# Fly-Back.net
KiCad netlist of a schematic drawn in Altium Designer
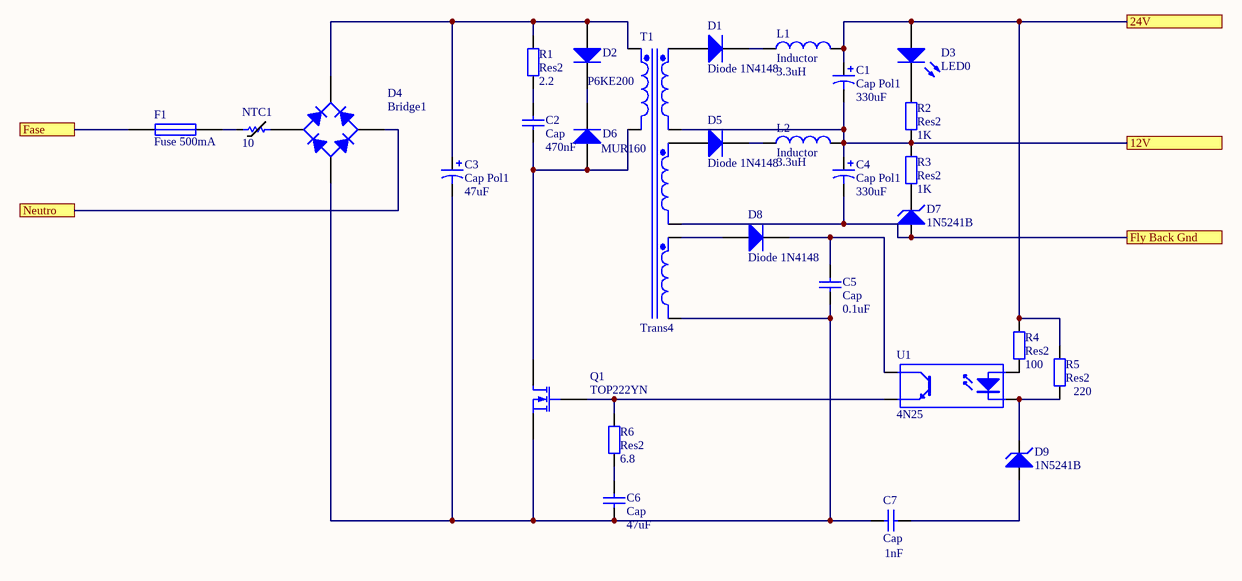
[diagram p0: Fly-Back.SchDoc]

(export (version "E")
  (design (tool "Eeschema 10.0.6"))
  (components
    (comp (ref "C1")
      (value "Cap Pol1")
      (footprint "RB7.6-15")
      (description "Polarized Capacitor (Radial)")
      (fields (field (name "ALTIUM_VALUE") "330uF") (field (name "PUBLISHER") "Altium Limited"))
      (libsource (lib "Miscellaneous Devices") (part "Cap Pol1"))
    )
    (comp (ref "C2")
      (value "Cap")
      (footprint "RAD-0.3")
      (description "Capacitor")
      (fields (field (name "ALTIUM_VALUE") "470nF") (field (name "PUBLISHER") "Altium Limited"))
      (libsource (lib "Miscellaneous Devices") (part "Cap"))
    )
    (comp (ref "C3")
      (value "Cap Pol1")
      (footprint "RB7.6-15")
      (description "Polarized Capacitor (Radial)")
      (fields (field (name "ALTIUM_VALUE") "47uF") (field (name "PUBLISHER") "Altium Limited"))
      (libsource (lib "Miscellaneous Devices") (part "Cap Pol1"))
    )
    (comp (ref "C4")
      (value "Cap Pol1")
      (footprint "RB7.6-15")
      (description "Polarized Capacitor (Radial)")
      (fields (field (name "ALTIUM_VALUE") "330uF") (field (name "PUBLISHER") "Altium Limited"))
      (libsource (lib "Miscellaneous Devices") (part "Cap Pol1"))
    )
    (comp (ref "C5")
      (value "Cap")
      (footprint "RAD-0.3")
      (description "Capacitor")
      (fields (field (name "ALTIUM_VALUE") "0.1uF") (field (name "PUBLISHER") "Altium Limited"))
      (libsource (lib "Miscellaneous Devices") (part "Cap"))
    )
    (comp (ref "C6")
      (value "Cap")
      (footprint "RAD-0.3")
      (description "Capacitor")
      (fields (field (name "ALTIUM_VALUE") "47uF") (field (name "PUBLISHER") "Altium Limited"))
      (libsource (lib "Miscellaneous Devices") (part "Cap"))
    )
    (comp (ref "C7")
      (value "Cap")
      (footprint "RAD-0.3")
      (description "Capacitor")
      (fields (field (name "ALTIUM_VALUE") "1nF") (field (name "PUBLISHER") "Altium Limited"))
      (libsource (lib "Miscellaneous Devices") (part "Cap"))
    )
    (comp (ref "D1")
      (value "Diode 1N4148")
      (footprint "DO-35")
      (description "High Conductance Fast Diode")
      (fields (field (name "PUBLISHER") "Altium Limited"))
      (libsource (lib "Miscellaneous Devices") (part "Diode 1N4148"))
    )
    (comp (ref "D2")
      (value "P6KE200")
      (footprint "DO-35")
      (description "High Conductance Fast Diode")
      (fields (field (name "PUBLISHER") "Altium Limited"))
      (libsource (lib "Miscellaneous Devices") (part "Diode 1N4148"))
    )
    (comp (ref "D3")
      (value "LED0")
      (footprint "LED-0")
      (description "Typical INFRARED GaAs LED")
      (fields (field (name "PUBLISHER") "Altium Limited"))
      (libsource (lib "Miscellaneous Devices") (part "LED0"))
    )
    (comp (ref "D4")
      (value "Bridge1")
      (footprint "D-38")
      (description "Full Wave Diode Bridge")
      (fields (field (name "PUBLISHER") "Altium Limited"))
      (libsource (lib "Miscellaneous Devices") (part "Bridge1"))
    )
    (comp (ref "D5")
      (value "Diode 1N4148")
      (footprint "DO-35")
      (description "High Conductance Fast Diode")
      (fields (field (name "PUBLISHER") "Altium Limited"))
      (libsource (lib "Miscellaneous Devices") (part "Diode 1N4148"))
    )
    (comp (ref "D6")
      (value "MUR160")
      (footprint "DO-35")
      (description "High Conductance Fast Diode")
      (fields (field (name "PUBLISHER") "Altium Limited"))
      (libsource (lib "Miscellaneous Devices") (part "Diode 1N4148"))
    )
    (comp (ref "D7")
      (value "Diodo Zener")
      (footprint "DO-41")
      (fields (field (name "VALOR") "1N5241B"))
      (libsource (lib "RUF-Dispositivos-Grales") (part "Diodo Zener"))
    )
    (comp (ref "D8")
      (value "Diode 1N4148")
      (footprint "DO-35")
      (description "High Conductance Fast Diode")
      (fields (field (name "PUBLISHER") "Altium Limited"))
      (libsource (lib "Miscellaneous Devices") (part "Diode 1N4148"))
    )
    (comp (ref "D9")
      (value "Diodo Zener")
      (footprint "DO-41")
      (fields (field (name "VALOR") "1N5241B"))
      (libsource (lib "RUF-Dispositivos-Grales") (part "Diodo Zener"))
    )
    (comp (ref "F1")
      (value "Fuse 500mA")
      (footprint "PIN-W2/E2.8")
      (description "Fuse")
      (fields (field (name "PUBLISHER") "Altium Limited"))
      (libsource (lib "Miscellaneous Devices") (part "Fuse 1"))
    )
    (comp (ref "L1")
      (value "Inductor")
      (footprint "0402-A")
      (fields (field (name "ALTIUM_VALUE") "3.3uH") (field (name "PUBLISHER") "Altium Limited"))
      (libsource (lib "Miscellaneous Devices") (part "Inductor"))
    )
    (comp (ref "L2")
      (value "Inductor")
      (footprint "0402-A")
      (fields (field (name "ALTIUM_VALUE") "3.3uH") (field (name "PUBLISHER") "Altium Limited"))
      (libsource (lib "Miscellaneous Devices") (part "Inductor"))
    )
    (comp (ref "NTC1")
      (value "Termistor NTC")
      (footprint "R0805")
      (description "Termistor NTC SMD")
      (fields (field (name "VALOR") "10"))
      (libsource (lib "RUF-Dispositivos-Grales") (part "Termistor NTC"))
    )
    (comp (ref "Q1")
      (value "TOP222YN")
      (footprint "E3")
      (description "N-Channel MOSFET")
      (fields (field (name "PUBLISHER") "Altium Limited"))
      (libsource (lib "Miscellaneous Devices") (part "MOSFET-N"))
    )
    (comp (ref "R1")
      (value "Res2")
      (footprint "AXIAL-0.4")
      (description "Resistor")
      (fields (field (name "ALTIUM_VALUE") "2.2") (field (name "PUBLISHER") "Altium Limited"))
      (libsource (lib "Miscellaneous Devices") (part "Res2"))
    )
    (comp (ref "R2")
      (value "Res2")
      (footprint "AXIAL-0.4")
      (description "Resistor")
      (fields (field (name "ALTIUM_VALUE") "1K") (field (name "PUBLISHER") "Altium Limited"))
      (libsource (lib "Miscellaneous Devices") (part "Res2"))
    )
    (comp (ref "R3")
      (value "Res2")
      (footprint "AXIAL-0.4")
      (description "Resistor")
      (fields (field (name "ALTIUM_VALUE") "1K") (field (name "PUBLISHER") "Altium Limited"))
      (libsource (lib "Miscellaneous Devices") (part "Res2"))
    )
    (comp (ref "R4")
      (value "Res2")
      (footprint "AXIAL-0.4")
      (description "Resistor")
      (fields (field (name "ALTIUM_VALUE") "100") (field (name "PUBLISHER") "Altium Limited"))
      (libsource (lib "Miscellaneous Devices") (part "Res2"))
    )
    (comp (ref "R5")
      (value "Res2")
      (footprint "AXIAL-0.4")
      (description "Resistor")
      (fields (field (name "ALTIUM_VALUE") "220") (field (name "PUBLISHER") "Altium Limited"))
      (libsource (lib "Miscellaneous Devices") (part "Res2"))
    )
    (comp (ref "R6")
      (value "Res2")
      (footprint "AXIAL-0.4")
      (description "Resistor")
      (fields (field (name "ALTIUM_VALUE") "6.8") (field (name "PUBLISHER") "Altium Limited"))
      (libsource (lib "Miscellaneous Devices") (part "Res2"))
    )
    (comp (ref "T1")
      (value "Trans4")
      (footprint "TRF_8")
      (description "Four-winding Transformer (Non-Ideal)")
      (fields (field (name "PUBLISHER") "Altium Limited"))
      (libsource (lib "Miscellaneous Devices") (part "Trans4"))
    )
    (comp (ref "U1")
      (value "4N25")
      (footprint "DIP-4")
      (description "4-Pin Phototransistor Optocoupler")
      (fields (field (name "PUBLISHER") "Altium Limited"))
      (libsource (lib "Miscellaneous Devices") (part "Optoisolator1"))
    )
  )
  (nets
    (net (code "1") (name "/12V") (class "Default")
      (node (ref "C1") (pin "2") (pinfunction "2_2") (pintype "passive"))
      (node (ref "C4") (pin "1") (pinfunction "1_1") (pintype "passive"))
      (node (ref "L2") (pin "2") (pinfunction "2_2") (pintype "passive"))
      (node (ref "R2") (pin "1") (pinfunction "1_1") (pintype "passive"))
      (node (ref "R3") (pin "2") (pinfunction "2_2") (pintype "passive"))
      (node (ref "T1") (pin "4") (pinfunction "Sec1-_4") (pintype "passive"))
    )
    (net (code "2") (name "/24V") (class "Default")
      (node (ref "C1") (pin "1") (pinfunction "1_1") (pintype "passive"))
      (node (ref "D3") (pin "1") (pinfunction "A_1") (pintype "passive"))
      (node (ref "L1") (pin "2") (pinfunction "2_2") (pintype "passive"))
      (node (ref "R4") (pin "2") (pinfunction "2_2") (pintype "passive"))
      (node (ref "R5") (pin "2") (pinfunction "2_2") (pintype "passive"))
    )
    (net (code "3") (name "/Fase") (class "Default")
      (node (ref "F1") (pin "1") (pinfunction "1_1") (pintype "passive"))
    )
    (net (code "4") (name "/Fly Back Gnd") (class "Default")
      (node (ref "C4") (pin "2") (pinfunction "2_2") (pintype "passive"))
      (node (ref "D7") (pin "1") (pinfunction "A_1") (pintype "passive"))
      (node (ref "T1") (pin "6") (pinfunction "Sec2-_6") (pintype "passive"))
    )
    (net (code "5") (name "/Neutro") (class "Default")
      (node (ref "D4") (pin "2") (pinfunction "C_2") (pintype "passive"))
    )
    (net (code "6") (name "Net-(C2-Pad2)") (class "Default")
      (node (ref "C2") (pin "2") (pinfunction "2_2") (pintype "passive"))
      (node (ref "R1") (pin "1") (pinfunction "1_1") (pintype "passive"))
    )
    (net (code "7") (name "Net-(C6-Pad2)") (class "Default")
      (node (ref "C6") (pin "2") (pinfunction "2_2") (pintype "passive"))
      (node (ref "R6") (pin "1") (pinfunction "1_1") (pintype "passive"))
    )
    (net (code "8") (name "Net-(D1-A)") (class "Default")
      (node (ref "D1") (pin "1") (pinfunction "A_1") (pintype "passive"))
      (node (ref "T1") (pin "3") (pinfunction "Sec1+_3") (pintype "passive"))
    )
    (net (code "9") (name "Net-(D1-K)") (class "Default")
      (node (ref "D1") (pin "2") (pinfunction "K_2") (pintype "passive"))
      (node (ref "L1") (pin "1") (pinfunction "1_1") (pintype "passive"))
    )
    (net (code "10") (name "Net-(D2-A)") (class "Default")
      (node (ref "C3") (pin "1") (pinfunction "1_1") (pintype "passive"))
      (node (ref "D2") (pin "1") (pinfunction "A_1") (pintype "passive"))
      (node (ref "D4") (pin "1") (pinfunction "K_1") (pintype "passive"))
      (node (ref "R1") (pin "2") (pinfunction "2_2") (pintype "passive"))
      (node (ref "T1") (pin "1") (pinfunction "Pri+_1") (pintype "passive"))
    )
    (net (code "11") (name "Net-(D2-K)") (class "Default")
      (node (ref "D2") (pin "2") (pinfunction "K_2") (pintype "passive"))
      (node (ref "D6") (pin "2") (pinfunction "K_2") (pintype "passive"))
    )
    (net (code "12") (name "Net-(D3-K)") (class "Default")
      (node (ref "D3") (pin "2") (pinfunction "K_2") (pintype "passive"))
      (node (ref "R2") (pin "2") (pinfunction "2_2") (pintype "passive"))
    )
    (net (code "13") (name "Net-(D4-A)") (class "Default")
      (node (ref "C3") (pin "2") (pinfunction "2_2") (pintype "passive"))
      (node (ref "C5") (pin "1") (pinfunction "1_1") (pintype "passive"))
      (node (ref "C6") (pin "1") (pinfunction "1_1") (pintype "passive"))
      (node (ref "C7") (pin "1") (pinfunction "1_1") (pintype "passive"))
      (node (ref "D4") (pin "3") (pinfunction "A_3") (pintype "passive"))
      (node (ref "Q1") (pin "3") (pinfunction "S_3") (pintype "passive"))
      (node (ref "T1") (pin "8") (pinfunction "Sec3-_8") (pintype "passive"))
    )
    (net (code "14") (name "Net-(D4-C-Pad4)") (class "Default")
      (node (ref "D4") (pin "4") (pinfunction "C_4") (pintype "passive"))
      (node (ref "NTC1") (pin "1") (pinfunction "1_1") (pintype "passive"))
    )
    (net (code "15") (name "Net-(D5-A)") (class "Default")
      (node (ref "D5") (pin "1") (pinfunction "A_1") (pintype "passive"))
      (node (ref "T1") (pin "5") (pinfunction "Sec2+_5") (pintype "passive"))
    )
    (net (code "16") (name "Net-(D5-K)") (class "Default")
      (node (ref "D5") (pin "2") (pinfunction "K_2") (pintype "passive"))
      (node (ref "L2") (pin "1") (pinfunction "1_1") (pintype "passive"))
    )
    (net (code "17") (name "Net-(D6-A)") (class "Default")
      (node (ref "C2") (pin "1") (pinfunction "1_1") (pintype "passive"))
      (node (ref "D6") (pin "1") (pinfunction "A_1") (pintype "passive"))
      (node (ref "Q1") (pin "1") (pinfunction "D_1") (pintype "passive"))
      (node (ref "T1") (pin "2") (pinfunction "Pri-_2") (pintype "passive"))
    )
    (net (code "18") (name "Net-(D7-K)") (class "Default")
      (node (ref "D7") (pin "2") (pinfunction "K_2") (pintype "passive"))
      (node (ref "R3") (pin "1") (pinfunction "1_1") (pintype "passive"))
    )
    (net (code "19") (name "Net-(D8-A)") (class "Default")
      (node (ref "D8") (pin "1") (pinfunction "A_1") (pintype "passive"))
      (node (ref "T1") (pin "7") (pinfunction "Sec3+_7") (pintype "passive"))
    )
    (net (code "20") (name "Net-(D8-K)") (class "Default")
      (node (ref "C5") (pin "2") (pinfunction "2_2") (pintype "passive"))
      (node (ref "D8") (pin "2") (pinfunction "K_2") (pintype "passive"))
      (node (ref "U1") (pin "4") (pinfunction "C_4") (pintype "passive"))
    )
    (net (code "21") (name "Net-(D9-A)") (class "Default")
      (node (ref "C7") (pin "2") (pinfunction "2_2") (pintype "passive"))
      (node (ref "D9") (pin "1") (pinfunction "A_1") (pintype "passive"))
    )
    (net (code "22") (name "Net-(D9-K)") (class "Default")
      (node (ref "D9") (pin "2") (pinfunction "K_2") (pintype "passive"))
      (node (ref "R5") (pin "1") (pinfunction "1_1") (pintype "passive"))
      (node (ref "U1") (pin "2") (pinfunction "K_2") (pintype "passive"))
    )
    (net (code "23") (name "Net-(F1-Pad2)") (class "Default")
      (node (ref "F1") (pin "2") (pinfunction "2_2") (pintype "passive"))
      (node (ref "NTC1") (pin "2") (pinfunction "2_2") (pintype "passive"))
    )
    (net (code "24") (name "Net-(Q1-G)") (class "Default")
      (node (ref "Q1") (pin "2") (pinfunction "G_2") (pintype "passive"))
      (node (ref "R6") (pin "2") (pinfunction "2_2") (pintype "passive"))
      (node (ref "U1") (pin "3") (pinfunction "E_3") (pintype "passive"))
    )
    (net (code "25") (name "Net-(U1-A)") (class "Default")
      (node (ref "R4") (pin "1") (pinfunction "1_1") (pintype "passive"))
      (node (ref "U1") (pin "1") (pinfunction "A_1") (pintype "passive"))
    )
  )
)
